# pan_tilt_lidar.net
KiCad netlist of a schematic drawn in EAGLE
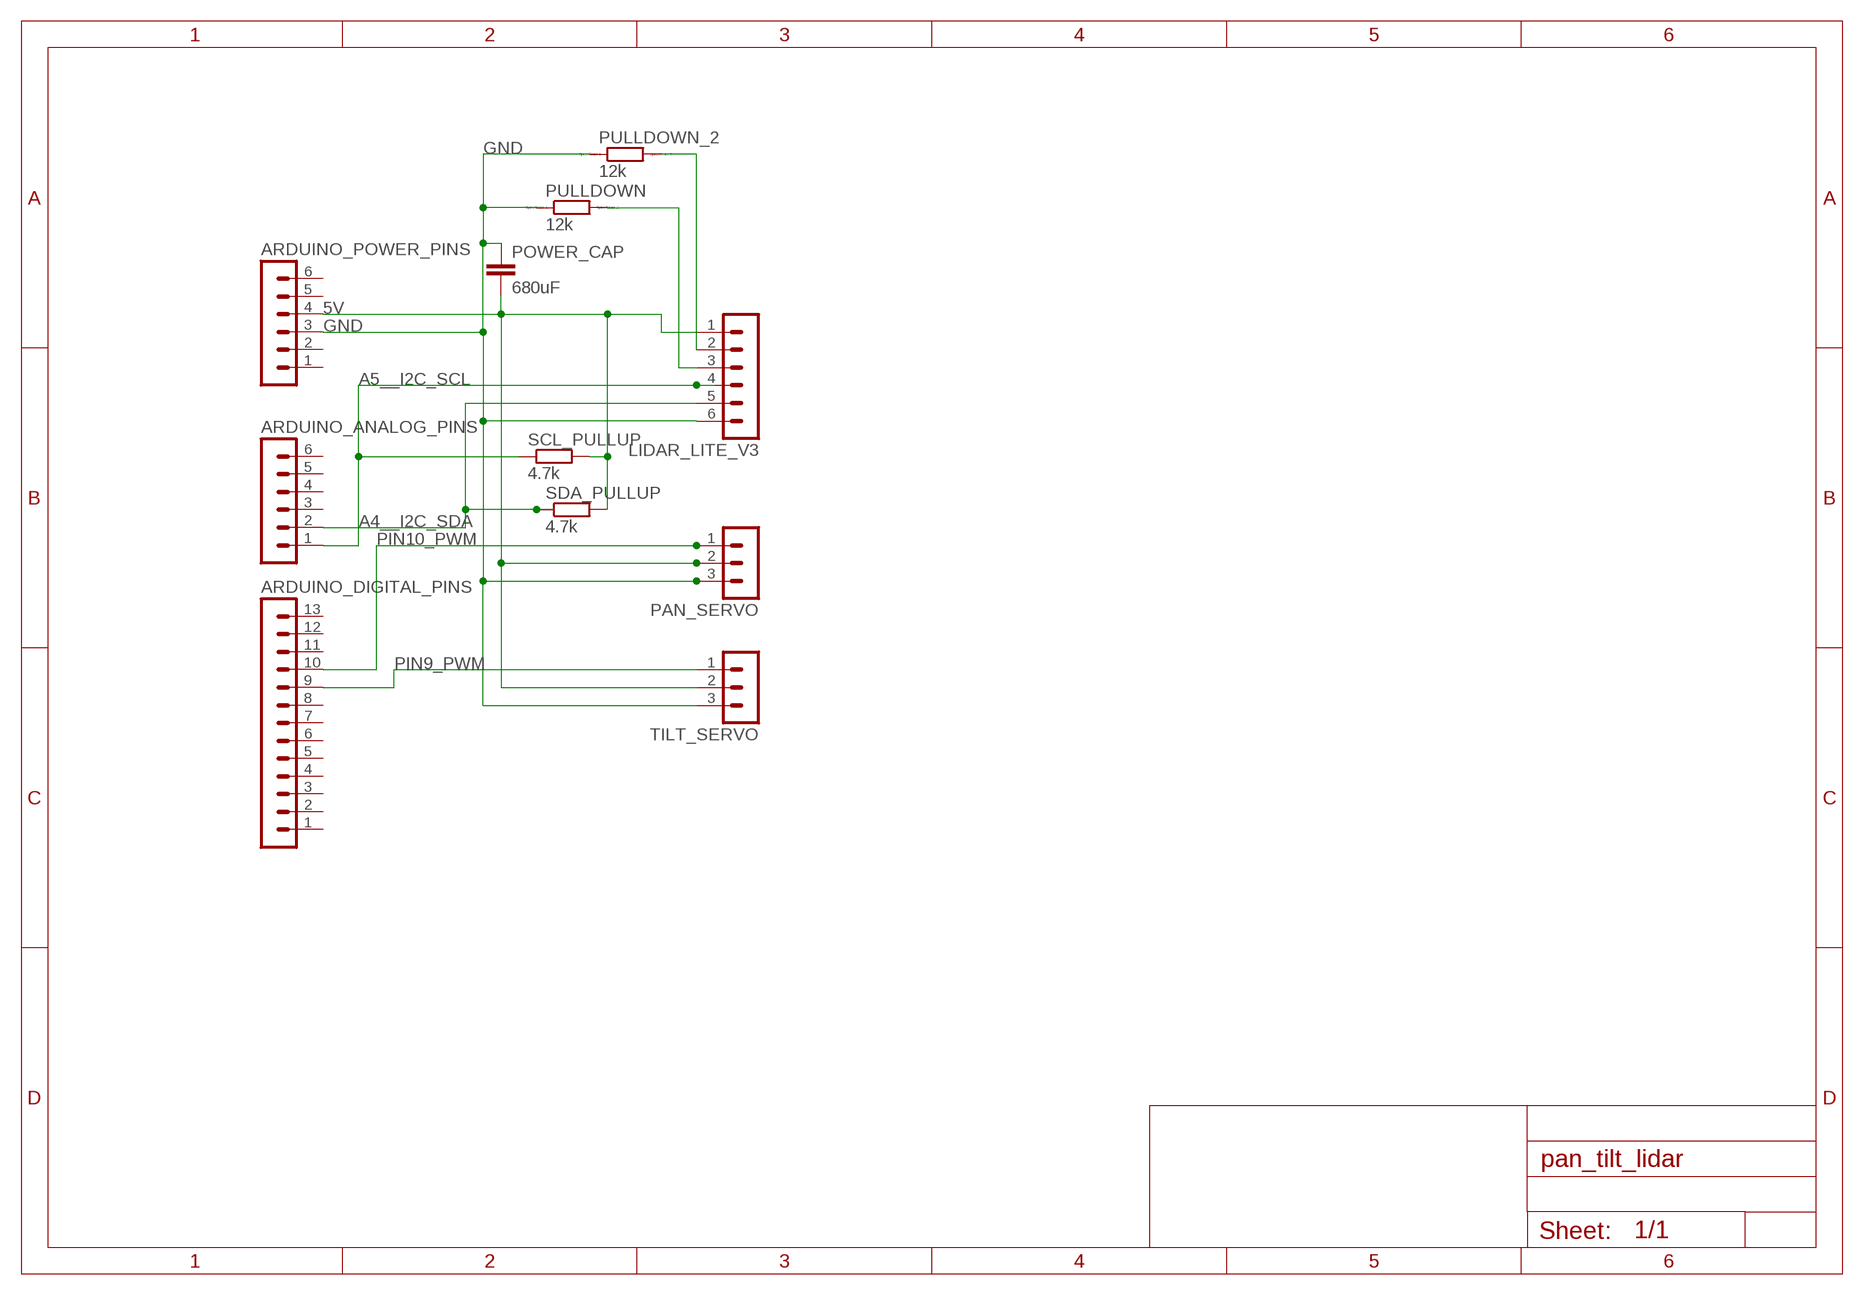
[diagram p0: schematic, sheet 1]

(export (version "E")
  (design (tool "Eeschema 10.0.6"))
  (components
    (comp (ref "ARDUINO_ANALOG_PINS")
      (value "MA06-1")
      (footprint "eagle-import:MA06-1")
      (libsource (lib "eagle-import") (part "MA06-1"))
    )
    (comp (ref "ARDUINO_DIGITAL_PINS")
      (value "MA13-1W")
      (footprint "eagle-import:MA13-1W")
      (libsource (lib "eagle-import") (part "MA13-1W"))
    )
    (comp (ref "ARDUINO_POWER_PINS")
      (value "MA06-1")
      (footprint "eagle-import:MA06-1")
      (libsource (lib "eagle-import") (part "MA06-1"))
    )
    (comp (ref "LIDAR_LITE_V3")
      (value "MA06-1")
      (footprint "eagle-import:MA06-1")
      (libsource (lib "eagle-import") (part "MA06-1"))
    )
    (comp (ref "PAN_SERVO")
      (value "MA03-1")
      (footprint "eagle-import:MA03-1")
      (libsource (lib "eagle-import") (part "MA03-1"))
    )
    (comp (ref "POWER_CAP")
      (value "680uF")
      (footprint "eagle-import:C2.5-4")
      (libsource (lib "eagle-import") (part "C2.5/4"))
    )
    (comp (ref "PULLDOWN")
      (value "12k")
      (footprint "eagle-import:0207_10")
      (libsource (lib "eagle-import") (part "R0207/10"))
    )
    (comp (ref "PULLDOWN_2")
      (value "12k")
      (footprint "eagle-import:0207_10")
      (libsource (lib "eagle-import") (part "R0207/10"))
    )
    (comp (ref "SCL_PULLUP")
      (value "4.7k")
      (footprint "eagle-import:0204V")
      (libsource (lib "eagle-import") (part "R-EU_0204/2V"))
    )
    (comp (ref "SDA_PULLUP")
      (value "4.7k")
      (footprint "eagle-import:0204V")
      (libsource (lib "eagle-import") (part "R-EU_0204/2V"))
    )
    (comp (ref "TILT_SERVO")
      (value "MA03-1")
      (footprint "eagle-import:MA03-1")
      (libsource (lib "eagle-import") (part "MA03-1"))
    )
  )
  (nets
    (net (code "1") (name "/5V") (class "Default")
      (node (ref "ARDUINO_POWER_PINS") (pin "4") (pinfunction "4_4") (pintype "passive"))
      (node (ref "LIDAR_LITE_V3") (pin "1") (pinfunction "1_1") (pintype "passive"))
      (node (ref "PAN_SERVO") (pin "2") (pinfunction "2_2") (pintype "passive"))
      (node (ref "POWER_CAP") (pin "2") (pinfunction "2_2") (pintype "passive"))
      (node (ref "SCL_PULLUP") (pin "2") (pinfunction "2_2") (pintype "passive"))
      (node (ref "SDA_PULLUP") (pin "2") (pinfunction "2_2") (pintype "passive"))
      (node (ref "TILT_SERVO") (pin "2") (pinfunction "2_2") (pintype "passive"))
    )
    (net (code "2") (name "/A4__I2C_SDA") (class "Default")
      (node (ref "ARDUINO_ANALOG_PINS") (pin "2") (pinfunction "2_2") (pintype "passive"))
      (node (ref "LIDAR_LITE_V3") (pin "5") (pinfunction "5_5") (pintype "passive"))
      (node (ref "SDA_PULLUP") (pin "1") (pinfunction "1_1") (pintype "passive"))
    )
    (net (code "3") (name "/A5__I2C_SCL") (class "Default")
      (node (ref "ARDUINO_ANALOG_PINS") (pin "1") (pinfunction "1_1") (pintype "passive"))
      (node (ref "LIDAR_LITE_V3") (pin "4") (pinfunction "4_4") (pintype "passive"))
      (node (ref "SCL_PULLUP") (pin "1") (pinfunction "1_1") (pintype "passive"))
    )
    (net (code "4") (name "/GND") (class "Default")
      (node (ref "ARDUINO_POWER_PINS") (pin "3") (pinfunction "3_3") (pintype "passive"))
      (node (ref "LIDAR_LITE_V3") (pin "6") (pinfunction "6_6") (pintype "passive"))
      (node (ref "PAN_SERVO") (pin "3") (pinfunction "3_3") (pintype "passive"))
      (node (ref "POWER_CAP") (pin "1") (pinfunction "1_1") (pintype "passive"))
      (node (ref "PULLDOWN") (pin "1") (pinfunction "1_1") (pintype "passive"))
      (node (ref "PULLDOWN_2") (pin "1") (pinfunction "1_1") (pintype "passive"))
      (node (ref "TILT_SERVO") (pin "3") (pinfunction "3_3") (pintype "passive"))
    )
    (net (code "5") (name "/PIN9_PWM") (class "Default")
      (node (ref "ARDUINO_DIGITAL_PINS") (pin "9") (pinfunction "9_9") (pintype "passive"))
      (node (ref "TILT_SERVO") (pin "1") (pinfunction "1_1") (pintype "passive"))
    )
    (net (code "6") (name "/PIN10_PWM") (class "Default")
      (node (ref "ARDUINO_DIGITAL_PINS") (pin "10") (pinfunction "10_10") (pintype "passive"))
      (node (ref "PAN_SERVO") (pin "1") (pinfunction "1_1") (pintype "passive"))
    )
    (net (code "7") (name "Net-(LIDAR_LITE_V3-Pad2)") (class "Default")
      (node (ref "LIDAR_LITE_V3") (pin "2") (pinfunction "2_2") (pintype "passive"))
      (node (ref "PULLDOWN_2") (pin "2") (pinfunction "2_2") (pintype "passive"))
    )
    (net (code "8") (name "Net-(LIDAR_LITE_V3-Pad3)") (class "Default")
      (node (ref "LIDAR_LITE_V3") (pin "3") (pinfunction "3_3") (pintype "passive"))
      (node (ref "PULLDOWN") (pin "2") (pinfunction "2_2") (pintype "passive"))
    )
    (net (code "9") (name "unconnected-(ARDUINO_ANALOG_PINS-Pad3)") (class "Default")
      (node (ref "ARDUINO_ANALOG_PINS") (pin "3") (pinfunction "3_3") (pintype "passive"))
    )
    (net (code "10") (name "unconnected-(ARDUINO_ANALOG_PINS-Pad4)") (class "Default")
      (node (ref "ARDUINO_ANALOG_PINS") (pin "4") (pinfunction "4_4") (pintype "passive"))
    )
    (net (code "11") (name "unconnected-(ARDUINO_ANALOG_PINS-Pad5)") (class "Default")
      (node (ref "ARDUINO_ANALOG_PINS") (pin "5") (pinfunction "5_5") (pintype "passive"))
    )
    (net (code "12") (name "unconnected-(ARDUINO_ANALOG_PINS-Pad6)") (class "Default")
      (node (ref "ARDUINO_ANALOG_PINS") (pin "6") (pinfunction "6_6") (pintype "passive"))
    )
    (net (code "13") (name "unconnected-(ARDUINO_DIGITAL_PINS-Pad1)") (class "Default")
      (node (ref "ARDUINO_DIGITAL_PINS") (pin "1") (pinfunction "1_1") (pintype "passive"))
    )
    (net (code "14") (name "unconnected-(ARDUINO_DIGITAL_PINS-Pad2)") (class "Default")
      (node (ref "ARDUINO_DIGITAL_PINS") (pin "2") (pinfunction "2_2") (pintype "passive"))
    )
    (net (code "15") (name "unconnected-(ARDUINO_DIGITAL_PINS-Pad3)") (class "Default")
      (node (ref "ARDUINO_DIGITAL_PINS") (pin "3") (pinfunction "3_3") (pintype "passive"))
    )
    (net (code "16") (name "unconnected-(ARDUINO_DIGITAL_PINS-Pad4)") (class "Default")
      (node (ref "ARDUINO_DIGITAL_PINS") (pin "4") (pinfunction "4_4") (pintype "passive"))
    )
    (net (code "17") (name "unconnected-(ARDUINO_DIGITAL_PINS-Pad5)") (class "Default")
      (node (ref "ARDUINO_DIGITAL_PINS") (pin "5") (pinfunction "5_5") (pintype "passive"))
    )
    (net (code "18") (name "unconnected-(ARDUINO_DIGITAL_PINS-Pad6)") (class "Default")
      (node (ref "ARDUINO_DIGITAL_PINS") (pin "6") (pinfunction "6_6") (pintype "passive"))
    )
    (net (code "19") (name "unconnected-(ARDUINO_DIGITAL_PINS-Pad7)") (class "Default")
      (node (ref "ARDUINO_DIGITAL_PINS") (pin "7") (pinfunction "7_7") (pintype "passive"))
    )
    (net (code "20") (name "unconnected-(ARDUINO_DIGITAL_PINS-Pad8)") (class "Default")
      (node (ref "ARDUINO_DIGITAL_PINS") (pin "8") (pinfunction "8_8") (pintype "passive"))
    )
    (net (code "21") (name "unconnected-(ARDUINO_DIGITAL_PINS-Pad11)") (class "Default")
      (node (ref "ARDUINO_DIGITAL_PINS") (pin "11") (pinfunction "11_11") (pintype "passive"))
    )
    (net (code "22") (name "unconnected-(ARDUINO_DIGITAL_PINS-Pad12)") (class "Default")
      (node (ref "ARDUINO_DIGITAL_PINS") (pin "12") (pinfunction "12_12") (pintype "passive"))
    )
    (net (code "23") (name "unconnected-(ARDUINO_DIGITAL_PINS-Pad13)") (class "Default")
      (node (ref "ARDUINO_DIGITAL_PINS") (pin "13") (pinfunction "13_13") (pintype "passive"))
    )
    (net (code "24") (name "unconnected-(ARDUINO_POWER_PINS-Pad1)") (class "Default")
      (node (ref "ARDUINO_POWER_PINS") (pin "1") (pinfunction "1_1") (pintype "passive"))
    )
    (net (code "25") (name "unconnected-(ARDUINO_POWER_PINS-Pad2)") (class "Default")
      (node (ref "ARDUINO_POWER_PINS") (pin "2") (pinfunction "2_2") (pintype "passive"))
    )
    (net (code "26") (name "unconnected-(ARDUINO_POWER_PINS-Pad5)") (class "Default")
      (node (ref "ARDUINO_POWER_PINS") (pin "5") (pinfunction "5_5") (pintype "passive"))
    )
    (net (code "27") (name "unconnected-(ARDUINO_POWER_PINS-Pad6)") (class "Default")
      (node (ref "ARDUINO_POWER_PINS") (pin "6") (pinfunction "6_6") (pintype "passive"))
    )
  )
)
